# Arduino_DDS_Shield_Rev_6.net
KiCad netlist of a schematic drawn in Altium Designer
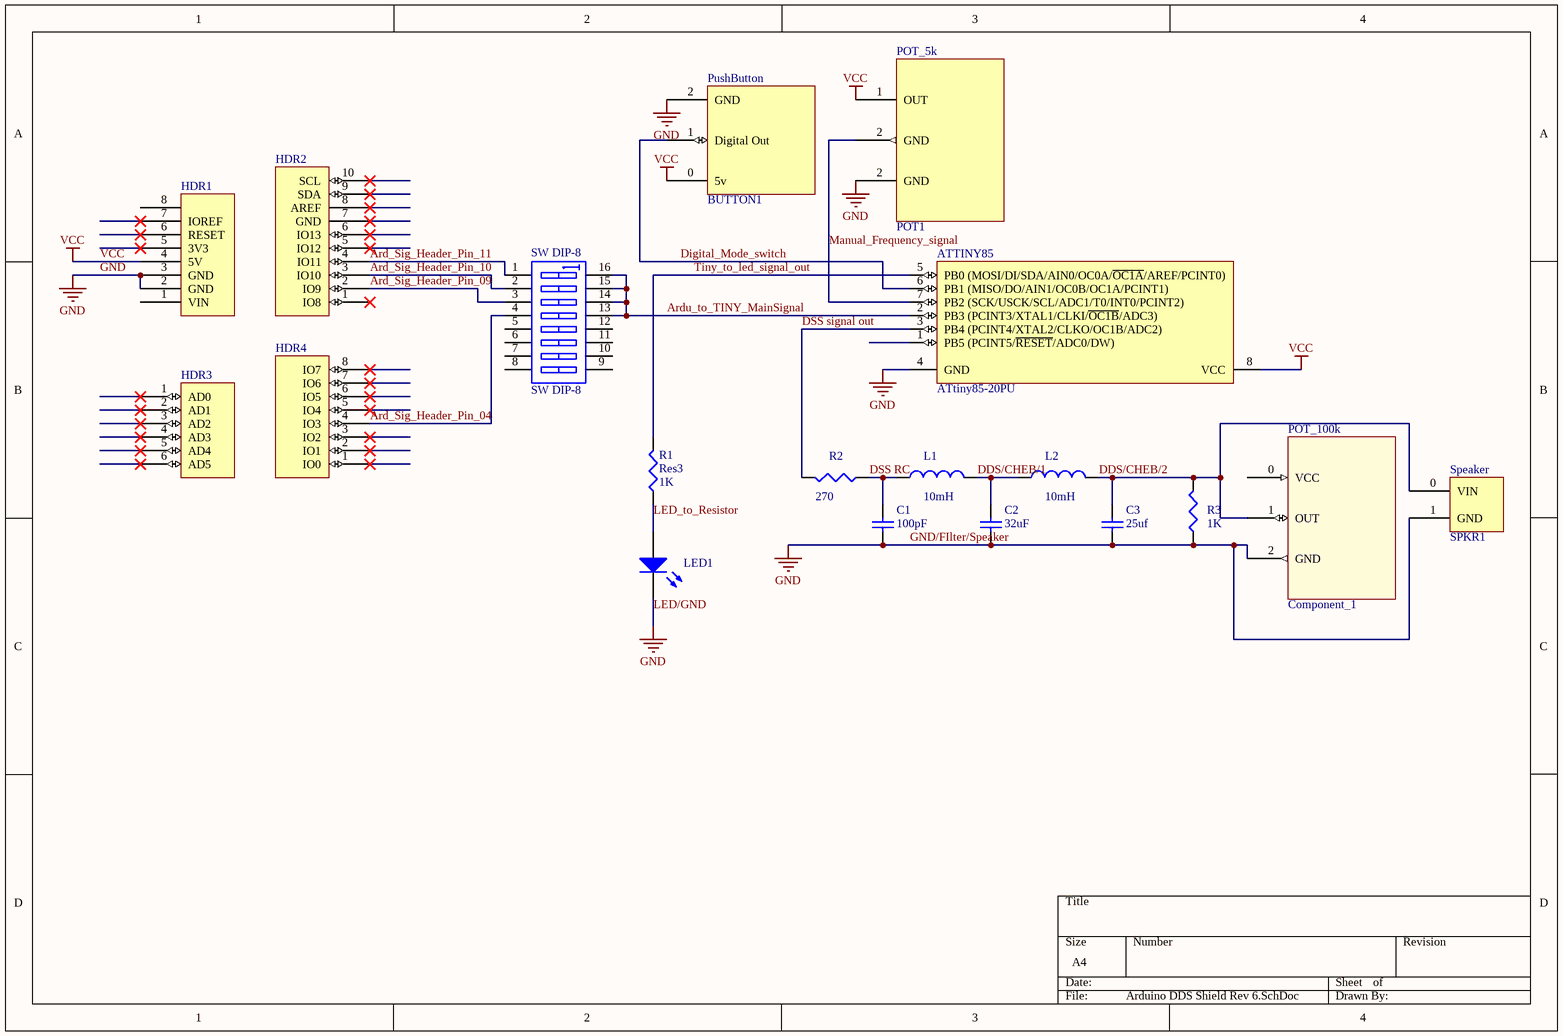
[diagram p0: Arduino DDS Shield Rev 6.SchDoc]

(export (version "E")
  (design (tool "Eeschema 10.0.6"))
  (components
    (comp (ref "ATTINY85")
      (value "ATtiny85-20PU")
      (footprint "8P3")
      (fields (field (name "PUBLISHER") "Altium Limited"))
      (libsource (lib "Atmel Microcontroller 8-Bit tinyAVR") (part "ATtiny85-20PU"))
    )
    (comp (ref "C1")
      (value "100pF")
      (footprint "1608[0603]")
      (description "Capacitor (Semiconductor SIM Model)")
      (fields (field (name "Comment") "Cap Semi") (field (name "PUBLISHER") "Altium Limited"))
      (libsource (lib "Miscellaneous Devices") (part "Cap Semi"))
    )
    (comp (ref "C2")
      (value "32uF")
      (footprint "1608[0603]")
      (description "Capacitor (Semiconductor SIM Model)")
      (fields (field (name "Comment") "Cap Semi") (field (name "PUBLISHER") "Altium Limited"))
      (libsource (lib "Miscellaneous Devices") (part "Cap Semi"))
    )
    (comp (ref "C3")
      (value "25uf")
      (footprint "1608[0603]")
      (description "Capacitor (Semiconductor SIM Model)")
      (fields (field (name "Comment") "Cap Semi") (field (name "PUBLISHER") "Altium Limited"))
      (libsource (lib "Miscellaneous Devices") (part "Cap Semi"))
    )
    (comp (ref "HDR1")
      (value "POWER_UNO")
      (footprint "Header 8x1 8.5mm")
      (libsource (lib "Header") (part "POWER_UNO"))
    )
    (comp (ref "HDR2")
      (value "IOH")
      (footprint "Header:Header 10x1 8.5mm")
      (libsource (lib "Header") (part "IOH"))
    )
    (comp (ref "HDR3")
      (value "AD")
      (footprint "Header:Header 6x1 8.5mm")
      (libsource (lib "Header") (part "AD"))
    )
    (comp (ref "HDR4") (value "IOL") (footprint "Header 8x1 8.5mm") (libsource (lib "Header") (part "IOL")))
    (comp (ref "L1")
      (value "10mH")
      (footprint "AXIAL-0.5")
      (description "Inductor")
      (fields (field (name "PUBLISHER") "Altium Limited"))
      (libsource (lib "Miscellaneous Devices") (part "Inductor"))
    )
    (comp (ref "L2")
      (value "10mH")
      (footprint "AXIAL-0.5")
      (description "Inductor")
      (fields (field (name "PUBLISHER") "Altium Limited"))
      (libsource (lib "Miscellaneous Devices") (part "Inductor"))
    )
    (comp (ref "LED1")
      (value "LED1")
      (footprint "LED-1")
      (description "Typical RED GaAs LED")
      (fields (field (name "PUBLISHER") "Altium Limited"))
      (libsource (lib "Miscellaneous Devices") (part "LED1"))
    )
    (comp (ref "POT_5k")
      (value "POT1")
      (footprint "Pot5k")
      (description "5k RES")
      (libsource (lib "PotLib_Rev_5") (part "Component_1"))
    )
    (comp (ref "POT_100k")
      (value "Component_1")
      (footprint "pot100k")
      (description "5k RES")
      (libsource (lib "PotLib_v_2") (part "Component_1"))
    )
    (comp (ref "PushButton")
      (value "BUTTON1")
      (footprint "PushButtonFrame")
      (libsource (lib "Pushbutton_V_5") (part "PushButton"))
    )
    (comp (ref "R1")
      (value "Res3")
      (footprint "J1-0603")
      (description "Resistor")
      (fields (field (name "ALTIUM_VALUE") "1K") (field (name "PUBLISHER") "Altium Limited"))
      (libsource (lib "Miscellaneous Devices") (part "Res3"))
    )
    (comp (ref "R2")
      (value "270")
      (footprint "J1-0603")
      (description "Resistor")
      (fields (field (name "Comment") "Res3") (field (name "PUBLISHER") "Altium Limited"))
      (libsource (lib "Miscellaneous Devices") (part "Res3"))
    )
    (comp (ref "R3")
      (value "1K")
      (footprint "J1-0603")
      (description "Resistor")
      (fields (field (name "Comment") "Res3") (field (name "PUBLISHER") "Altium Limited"))
      (libsource (lib "Miscellaneous Devices") (part "Res3"))
    )
    (comp (ref "Speaker")
      (value "SPKR1")
      (footprint "PCBComponent_1")
      (libsource (lib "Schlib1_rev_01") (part "Component_1"))
    )
    (comp (ref "SW DIP-8")
      (value "SW DIP-8")
      (footprint "DIP8posSolder")
      (description "DIP Switch, 8 Position, SPST")
      (fields (field (name "PUBLISHER") "Altium Limited"))
      (libsource (lib "Miscellaneous Devices") (part "SW DIP-8"))
    )
  )
  (nets
    (net (code "2") (name "/Ard_Sig_Header_Pin_04") (class "Default")
      (node (ref "HDR4") (pin "4") (pinfunction "IO3_4") (pintype "bidirectional"))
      (node (ref "SW DIP-8") (pin "4") (pinfunction "A4_4") (pintype "passive"))
    )
    (net (code "3") (name "/Ard_Sig_Header_Pin_09") (class "Default")
      (node (ref "HDR2") (pin "2") (pinfunction "IO9_2") (pintype "bidirectional"))
      (node (ref "SW DIP-8") (pin "3") (pinfunction "A3_3") (pintype "passive"))
    )
    (net (code "4") (name "/Ard_Sig_Header_Pin_10") (class "Default")
      (node (ref "HDR2") (pin "3") (pinfunction "IO10_3") (pintype "bidirectional"))
      (node (ref "SW DIP-8") (pin "2") (pinfunction "A2_2") (pintype "passive"))
    )
    (net (code "5") (name "/Ard_Sig_Header_Pin_11") (class "Default")
      (node (ref "HDR2") (pin "4") (pinfunction "IO11_4") (pintype "bidirectional"))
      (node (ref "SW DIP-8") (pin "1") (pinfunction "A1_1") (pintype "passive"))
    )
    (net (code "6") (name "/Ardu_to_TINY_MainSignal") (class "Default")
      (node (ref "ATTINY85") (pin "2") (pinfunction "PB3_(PCINT3/XTAL1/CLKI/~{OC1B}/ADC3)_2") (pintype "bidirectional"))
      (node (ref "SW DIP-8") (pin "13") (pinfunction "B4_13") (pintype "passive"))
      (node (ref "SW DIP-8") (pin "14") (pinfunction "B3_14") (pintype "passive"))
      (node (ref "SW DIP-8") (pin "15") (pinfunction "B2_15") (pintype "passive"))
      (node (ref "SW DIP-8") (pin "16") (pinfunction "B1_16") (pintype "passive"))
    )
    (net (code "7") (name "/DDS{slash}CHEB{slash}1") (class "Default")
      (node (ref "C2") (pin "2") (pinfunction "2_2") (pintype "passive"))
      (node (ref "L1") (pin "2") (pinfunction "2_2") (pintype "passive"))
      (node (ref "L2") (pin "1") (pinfunction "1_1") (pintype "passive"))
    )
    (net (code "8") (name "/DDS{slash}CHEB{slash}2") (class "Default")
      (node (ref "C3") (pin "2") (pinfunction "2_2") (pintype "passive"))
      (node (ref "L2") (pin "2") (pinfunction "2_2") (pintype "passive"))
      (node (ref "POT_100k") (pin "1") (pinfunction "OUT_1") (pintype "bidirectional"))
      (node (ref "R3") (pin "2") (pinfunction "2_2") (pintype "passive"))
      (node (ref "Speaker") (pin "0") (pinfunction "VIN_0") (pintype "power_in"))
    )
    (net (code "9") (name "/DSS RC") (class "Default")
      (node (ref "C1") (pin "2") (pinfunction "2_2") (pintype "passive"))
      (node (ref "L1") (pin "1") (pinfunction "1_1") (pintype "passive"))
      (node (ref "R2") (pin "1") (pinfunction "1_1") (pintype "passive"))
    )
    (net (code "10") (name "/DSS signal out") (class "Default")
      (node (ref "ATTINY85") (pin "3") (pinfunction "PB4_(PCINT4/XTAL2/CLKO/OC1B/ADC2)_3") (pintype "bidirectional"))
      (node (ref "R2") (pin "2") (pinfunction "2_2") (pintype "passive"))
    )
    (net (code "11") (name "/Digital_Mode_switch") (class "Default")
      (node (ref "ATTINY85") (pin "6") (pinfunction "PB1_(MISO/DO/AIN1/OC0B/OC1A/PCINT1)_6") (pintype "bidirectional"))
      (node (ref "PushButton") (pin "1") (pinfunction "Digital_Out_1") (pintype "bidirectional"))
    )
    (net (code "12") (name "/LED_to_Resistor") (class "Default")
      (node (ref "LED1") (pin "1") (pinfunction "A_1") (pintype "passive"))
      (node (ref "R1") (pin "1") (pinfunction "1_1") (pintype "passive"))
    )
    (net (code "13") (name "/Manual_Frequency_signal") (class "Default")
      (node (ref "ATTINY85") (pin "7") (pinfunction "PB2_(SCK/USCK/SCL/ADC1/T0/INT0/PCINT2)_7") (pintype "bidirectional"))
      (node (ref "POT_5k") (pin "2") (pinfunction "GND_2") (pintype "output"))
    )
    (net (code "14") (name "/Tiny_to_led_signal_out") (class "Default")
      (node (ref "ATTINY85") (pin "5") (pinfunction "PB0_(MOSI/DI/SDA/AIN0/OC0A/~{OC1A}/AREF/PCINT0)_5") (pintype "bidirectional"))
      (node (ref "R1") (pin "2") (pinfunction "2_2") (pintype "passive"))
    )
    (net (code "15") (name "GND") (class "Default")
      (node (ref "ATTINY85") (pin "4") (pinfunction "GND_4") (pintype "power_in"))
      (node (ref "C1") (pin "1") (pinfunction "1_1") (pintype "passive"))
      (node (ref "C2") (pin "1") (pinfunction "1_1") (pintype "passive"))
      (node (ref "C3") (pin "1") (pinfunction "1_1") (pintype "passive"))
      (node (ref "HDR1") (pin "2") (pinfunction "GND_2") (pintype "power_in"))
      (node (ref "HDR1") (pin "3") (pinfunction "GND_3") (pintype "power_in"))
      (node (ref "LED1") (pin "2") (pinfunction "K_2") (pintype "passive"))
      (node (ref "POT_100k") (pin "2") (pinfunction "GND_2") (pintype "output"))
      (node (ref "POT_5k") (pin "2") (pinfunction "GND_2") (pintype "power_in"))
      (node (ref "PushButton") (pin "2") (pinfunction "GND_2") (pintype "power_in"))
      (node (ref "R3") (pin "1") (pinfunction "1_1") (pintype "passive"))
      (node (ref "Speaker") (pin "1") (pinfunction "GND_1") (pintype "power_in"))
    )
    (net (code "16") (name "VCC") (class "Default")
      (node (ref "ATTINY85") (pin "8") (pinfunction "VCC_8") (pintype "power_in"))
      (node (ref "HDR1") (pin "4") (pinfunction "5V_4") (pintype "power_in"))
      (node (ref "POT_5k") (pin "1") (pinfunction "OUT_1") (pintype "power_in"))
      (node (ref "PushButton") (pin "0") (pinfunction "5v_0") (pintype "power_in"))
    )
    (net (code "17") (name "unconnected-(ATTINY85-PB5_(PCINT5{slash}~{RESET}{slash}ADC0{slash}DW)-Pad1)") (class "Default")
      (node (ref "ATTINY85") (pin "1") (pinfunction "PB5_(PCINT5/~{RESET}/ADC0/DW)_1") (pintype "bidirectional"))
    )
    (net (code "18") (name "unconnected-(HDR1-3V3-Pad5)") (class "Default")
      (node (ref "HDR1") (pin "5") (pinfunction "3V3_5") (pintype "power_in+no_connect"))
    )
    (net (code "19") (name "unconnected-(HDR1-IOREF-Pad7)") (class "Default")
      (node (ref "HDR1") (pin "7") (pinfunction "IOREF_7") (pintype "power_in+no_connect"))
    )
    (net (code "20") (name "unconnected-(HDR1-Pad8)") (class "Default")
      (node (ref "HDR1") (pin "8") (pintype "passive"))
    )
    (net (code "21") (name "unconnected-(HDR1-RESET-Pad6)") (class "Default")
      (node (ref "HDR1") (pin "6") (pinfunction "RESET_6") (pintype "passive+no_connect"))
    )
    (net (code "22") (name "unconnected-(HDR1-VIN-Pad1)") (class "Default")
      (node (ref "HDR1") (pin "1") (pinfunction "VIN_1") (pintype "power_in"))
    )
    (net (code "23") (name "unconnected-(HDR2-AREF-Pad8)") (class "Default")
      (node (ref "HDR2") (pin "8") (pinfunction "AREF_8") (pintype "passive+no_connect"))
    )
    (net (code "24") (name "unconnected-(HDR2-GND-Pad7)") (class "Default")
      (node (ref "HDR2") (pin "7") (pinfunction "GND_7") (pintype "power_in+no_connect"))
    )
    (net (code "25") (name "unconnected-(HDR2-IO8-Pad1)") (class "Default")
      (node (ref "HDR2") (pin "1") (pinfunction "IO8_1") (pintype "bidirectional+no_connect"))
    )
    (net (code "26") (name "unconnected-(HDR2-IO12-Pad5)") (class "Default")
      (node (ref "HDR2") (pin "5") (pinfunction "IO12_5") (pintype "bidirectional+no_connect"))
    )
    (net (code "27") (name "unconnected-(HDR2-IO13-Pad6)") (class "Default")
      (node (ref "HDR2") (pin "6") (pinfunction "IO13_6") (pintype "bidirectional+no_connect"))
    )
    (net (code "28") (name "unconnected-(HDR2-SCL-Pad10)") (class "Default")
      (node (ref "HDR2") (pin "10") (pinfunction "SCL_10") (pintype "bidirectional+no_connect"))
    )
    (net (code "29") (name "unconnected-(HDR2-SDA-Pad9)") (class "Default")
      (node (ref "HDR2") (pin "9") (pinfunction "SDA_9") (pintype "bidirectional+no_connect"))
    )
    (net (code "30") (name "unconnected-(HDR3-AD0-Pad1)") (class "Default")
      (node (ref "HDR3") (pin "1") (pinfunction "AD0_1") (pintype "bidirectional+no_connect"))
    )
    (net (code "31") (name "unconnected-(HDR3-AD1-Pad2)") (class "Default")
      (node (ref "HDR3") (pin "2") (pinfunction "AD1_2") (pintype "bidirectional+no_connect"))
    )
    (net (code "32") (name "unconnected-(HDR3-AD2-Pad3)") (class "Default")
      (node (ref "HDR3") (pin "3") (pinfunction "AD2_3") (pintype "bidirectional+no_connect"))
    )
    (net (code "33") (name "unconnected-(HDR3-AD3-Pad4)") (class "Default")
      (node (ref "HDR3") (pin "4") (pinfunction "AD3_4") (pintype "bidirectional+no_connect"))
    )
    (net (code "34") (name "unconnected-(HDR3-AD4-Pad5)") (class "Default")
      (node (ref "HDR3") (pin "5") (pinfunction "AD4_5") (pintype "bidirectional+no_connect"))
    )
    (net (code "35") (name "unconnected-(HDR3-AD5-Pad6)") (class "Default")
      (node (ref "HDR3") (pin "6") (pinfunction "AD5_6") (pintype "bidirectional+no_connect"))
    )
    (net (code "36") (name "unconnected-(HDR4-IO0-Pad1)") (class "Default")
      (node (ref "HDR4") (pin "1") (pinfunction "IO0_1") (pintype "bidirectional+no_connect"))
    )
    (net (code "37") (name "unconnected-(HDR4-IO1-Pad2)") (class "Default")
      (node (ref "HDR4") (pin "2") (pinfunction "IO1_2") (pintype "bidirectional+no_connect"))
    )
    (net (code "38") (name "unconnected-(HDR4-IO2-Pad3)") (class "Default")
      (node (ref "HDR4") (pin "3") (pinfunction "IO2_3") (pintype "bidirectional+no_connect"))
    )
    (net (code "39") (name "unconnected-(HDR4-IO4-Pad5)") (class "Default")
      (node (ref "HDR4") (pin "5") (pinfunction "IO4_5") (pintype "bidirectional+no_connect"))
    )
    (net (code "40") (name "unconnected-(HDR4-IO5-Pad6)") (class "Default")
      (node (ref "HDR4") (pin "6") (pinfunction "IO5_6") (pintype "bidirectional+no_connect"))
    )
    (net (code "41") (name "unconnected-(HDR4-IO6-Pad7)") (class "Default")
      (node (ref "HDR4") (pin "7") (pinfunction "IO6_7") (pintype "bidirectional+no_connect"))
    )
    (net (code "42") (name "unconnected-(HDR4-IO7-Pad8)") (class "Default")
      (node (ref "HDR4") (pin "8") (pinfunction "IO7_8") (pintype "bidirectional+no_connect"))
    )
    (net (code "43") (name "unconnected-(POT_100k-VCC-Pad0)") (class "Default")
      (node (ref "POT_100k") (pin "0") (pinfunction "VCC_0") (pintype "input"))
    )
    (net (code "44") (name "unconnected-(SW DIP-8-A5-Pad5)") (class "Default")
      (node (ref "SW DIP-8") (pin "5") (pinfunction "A5_5") (pintype "passive"))
    )
    (net (code "45") (name "unconnected-(SW DIP-8-A6-Pad6)") (class "Default")
      (node (ref "SW DIP-8") (pin "6") (pinfunction "A6_6") (pintype "passive"))
    )
    (net (code "46") (name "unconnected-(SW DIP-8-A7-Pad7)") (class "Default")
      (node (ref "SW DIP-8") (pin "7") (pinfunction "A7_7") (pintype "passive"))
    )
    (net (code "47") (name "unconnected-(SW DIP-8-A8-Pad8)") (class "Default")
      (node (ref "SW DIP-8") (pin "8") (pinfunction "A8_8") (pintype "passive"))
    )
    (net (code "48") (name "unconnected-(SW DIP-8-B5-Pad12)") (class "Default")
      (node (ref "SW DIP-8") (pin "12") (pinfunction "B5_12") (pintype "passive"))
    )
    (net (code "49") (name "unconnected-(SW DIP-8-B6-Pad11)") (class "Default")
      (node (ref "SW DIP-8") (pin "11") (pinfunction "B6_11") (pintype "passive"))
    )
    (net (code "50") (name "unconnected-(SW DIP-8-B7-Pad10)") (class "Default")
      (node (ref "SW DIP-8") (pin "10") (pinfunction "B7_10") (pintype "passive"))
    )
    (net (code "51") (name "unconnected-(SW DIP-8-B8-Pad9)") (class "Default")
      (node (ref "SW DIP-8") (pin "9") (pinfunction "B8_9") (pintype "passive"))
    )
  )
)
